# hv_io_precharge.net
KiCad netlist of a schematic drawn in Altium Designer
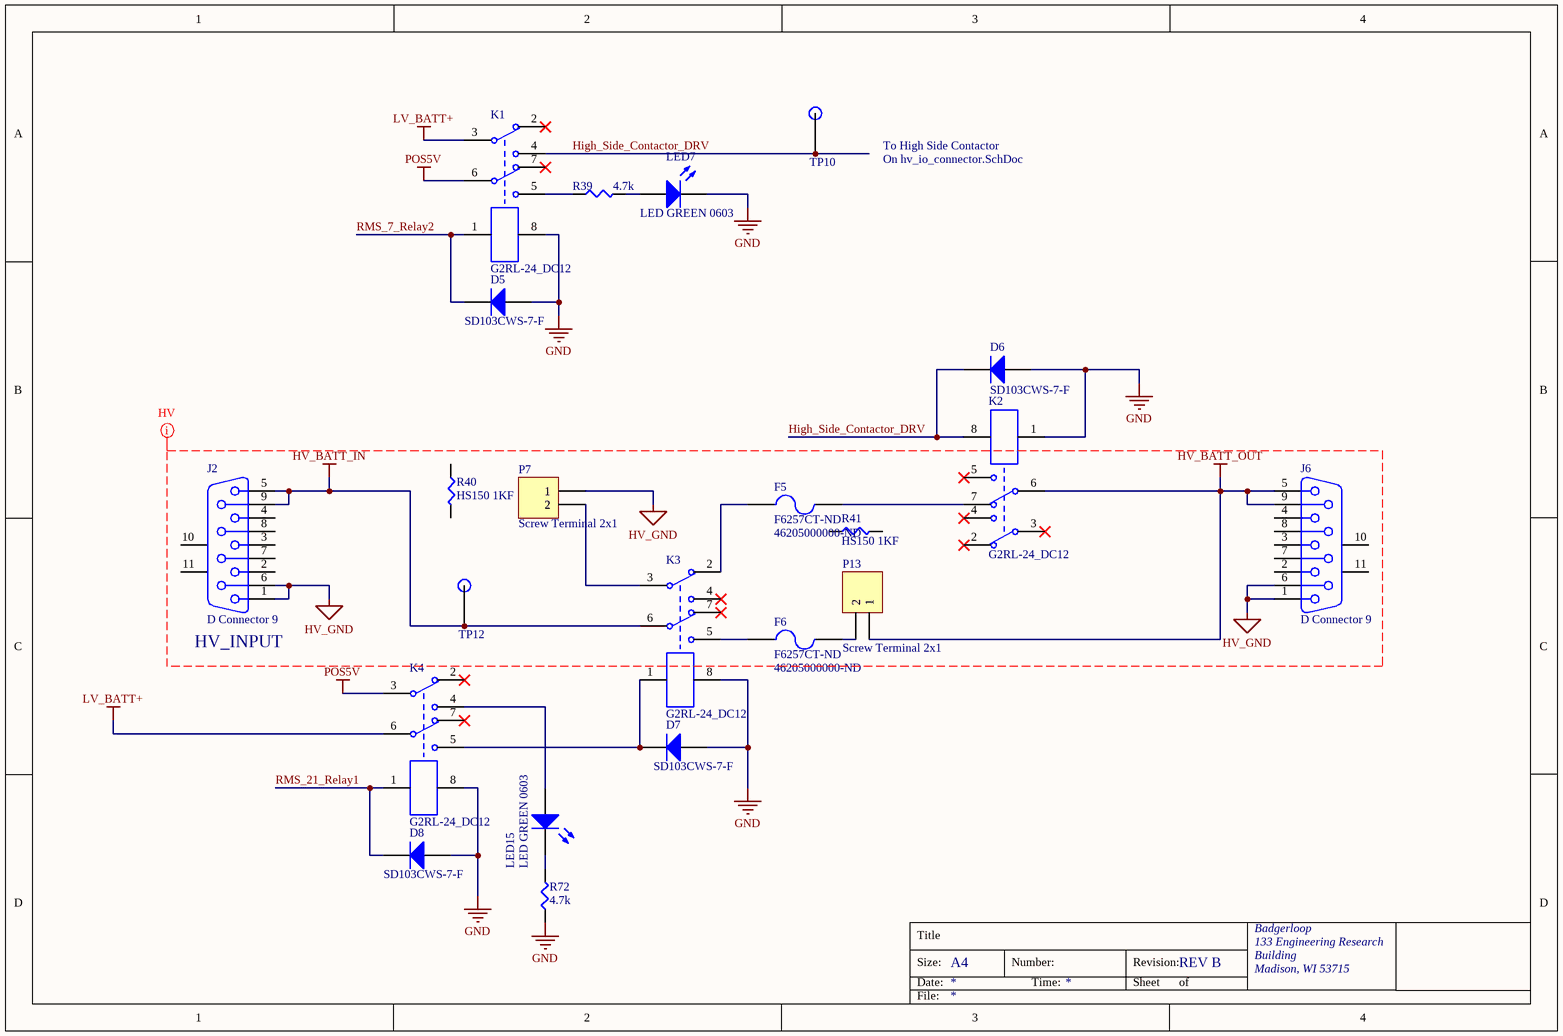
[diagram p0: hv_io_precharge.SchDoc]

(export (version "E")
  (design (tool "Eeschema 10.0.6"))
  (components
    (comp (ref "D5")
      (value "SD103CWS-7-F")
      (footprint "SODFL250X110-2N")
      (description "DIODE GEN PURP 20V 350MA SOD323")
      (fields (field (name "MANUFACTURER") "Diodes Incorporated"))
      (libsource (lib "misc") (part "Diode General Purpose_2"))
    )
    (comp (ref "D6")
      (value "SD103CWS-7-F")
      (footprint "SODFL250X110-2N")
      (description "DIODE GEN PURP 20V 350MA SOD323")
      (fields (field (name "MANUFACTURER") "Diodes Incorporated"))
      (libsource (lib "misc") (part "Diode General Purpose_2"))
    )
    (comp (ref "D7")
      (value "SD103CWS-7-F")
      (footprint "SODFL250X110-2N")
      (description "DIODE GEN PURP 20V 350MA SOD323")
      (fields (field (name "MANUFACTURER") "Diodes Incorporated"))
      (libsource (lib "misc") (part "Diode General Purpose_2"))
    )
    (comp (ref "D8")
      (value "SD103CWS-7-F")
      (footprint "SODFL250X110-2N")
      (description "DIODE GEN PURP 20V 350MA SOD323")
      (fields (field (name "MANUFACTURER") "Diodes Incorporated"))
      (libsource (lib "misc") (part "Diode General Purpose_2"))
    )
    (comp (ref "F5")
      (value "F6257CT-ND")
      (footprint "F6257CT-ND")
      (description "FUSE BOARD MNT 500MA 350VAC/VDC")
      (fields
        (field (name "MANUFACTURER") "Littelfuse")
        (field (name "MANUFACTURER PART NUMBER") "46205000000")
        (field (name "SUPPLIER PART NUMBER 1") "46205000000-ND")
      )
      (libsource (lib "misc") (part "F6257CT-ND"))
    )
    (comp (ref "F6")
      (value "F6257CT-ND")
      (footprint "F6257CT-ND")
      (description "FUSE BOARD MNT 500MA 350VAC/VDC")
      (fields
        (field (name "MANUFACTURER") "Littelfuse")
        (field (name "MANUFACTURER PART NUMBER") "46205000000")
        (field (name "SUPPLIER PART NUMBER 1") "46205000000-ND")
      )
      (libsource (lib "misc") (part "F6257CT-ND"))
    )
    (comp (ref "J2")
      (value "D Connector 9")
      (footprint "DSUB1.385-2H9")
      (description "Receptacle Assembly, 9 Position, Right Angle")
      (fields (field (name "PUBLISHER") "Altium Limited"))
      (libsource (lib "altium-import") (part "root_1_D Connector 9_"))
    )
    (comp (ref "J6")
      (value "D Connector 9")
      (footprint "DSUB1.385-2H9")
      (description "Receptacle Assembly, 9 Position, Right Angle")
      (fields (field (name "PUBLISHER") "Altium Limited"))
      (libsource (lib "altium-import") (part "root_1_mirrored_D Connector 9_"))
    )
    (comp (ref "K1")
      (value "G2RL-24_DC12")
      (footprint "G2RL")
      (description "RELAY GEN PURPOSE DPDT 8A 12V")
      (fields (field (name "MANUFACTURER") "Omron Electronics"))
      (libsource (lib "misc") (part "G2RL-24_DC12"))
    )
    (comp (ref "K2")
      (value "G2RL-24_DC12")
      (footprint "G2RL")
      (description "RELAY GEN PURPOSE DPDT 8A 12V")
      (fields (field (name "MANUFACTURER") "Omron Electronics"))
      (libsource (lib "misc") (part "G2RL-24_DC12"))
    )
    (comp (ref "K3")
      (value "G2RL-24_DC12")
      (footprint "G2RL")
      (description "RELAY GEN PURPOSE DPDT 8A 12V")
      (fields (field (name "MANUFACTURER") "Omron Electronics"))
      (libsource (lib "misc") (part "G2RL-24_DC12"))
    )
    (comp (ref "K4")
      (value "G2RL-24_DC12")
      (footprint "G2RL")
      (description "RELAY GEN PURPOSE DPDT 8A 12V")
      (fields (field (name "MANUFACTURER") "Omron Electronics"))
      (libsource (lib "misc") (part "G2RL-24_DC12"))
    )
    (comp (ref "LED7")
      (value "LED GREEN 0603")
      (footprint "LED 0603 GREEN")
      (fields (field (name "MANUFACTURER") "Lite-On Inc."))
      (libsource (lib "misc") (part "LED GREEN 0603"))
    )
    (comp (ref "LED15")
      (value "LED GREEN 0603")
      (footprint "LED 0603 GREEN")
      (fields (field (name "MANUFACTURER") "Lite-On Inc."))
      (libsource (lib "misc") (part "LED GREEN 0603"))
    )
    (comp (ref "P7")
      (value "Screw Terminal 2x1")
      (footprint "2POS TERM BLOCK")
      (description "Screw Terminal, 2-Pin")
      (libsource (lib "") (part "Screw Terminal 2x1_1"))
    )
    (comp (ref "P13")
      (value "Screw Terminal 2x1")
      (footprint "2POS TERM BLOCK")
      (description "Screw Terminal, 2-Pin")
      (libsource (lib "connector") (part "Screw Terminal 2x1"))
    )
    (comp (ref "R39")
      (value "4.7k")
      (footprint "SMD-0402-RES")
      (description "RES SMD 4.7K OHM 5% 1/10W 0402")
      (fields (field (name "PART NUMBER") "ERJ-2GEJ472X") (field (name "DIGI-KEY PART NUMBER") "P4.7KJCT-ND"))
      (libsource (lib "resistor") (part "ERJ-2GEJ472X"))
    )
    (comp (ref "R40")
      (value "HS150 1KF")
      (footprint "HS150 1KF")
      (description "1K Power Resistor")
      (fields (field (name "MANUFACTURER") "Ohmite"))
      (libsource (lib "temp") (part "HS150 1KF"))
    )
    (comp (ref "R41")
      (value "HS150 1KF")
      (footprint "HS150 1KF")
      (description "1K Power Resistor")
      (fields (field (name "MANUFACTURER") "Ohmite"))
      (libsource (lib "temp") (part "HS150 1KF"))
    )
    (comp (ref "R72")
      (value "4.7k")
      (footprint "SMD-0402-RES")
      (description "RES SMD 4.7K OHM 5% 1/10W 0402")
      (fields (field (name "PART NUMBER") "ERJ-2GEJ472X") (field (name "DIGI-KEY PART NUMBER") "P4.7KJCT-ND"))
      (libsource (lib "resistor") (part "ERJ-2GEJ472X"))
    )
    (comp (ref "TP10") (value "TP") (footprint "Test Point") (libsource (lib "misc") (part "TP")))
    (comp (ref "TP12") (value "TP") (footprint "Test Point") (libsource (lib "misc") (part "TP")))
  )
  (nets
    (net (code "1") (name "/High_Side_Contactor_DRV") (class "Default")
      (node (ref "D6") (pin "2") (pinfunction "K_2") (pintype "passive"))
      (node (ref "K1") (pin "4") (pinfunction "4_4") (pintype "passive"))
      (node (ref "K2") (pin "8") (pinfunction "8_8") (pintype "passive"))
      (node (ref "TP10") (pin "1") (pinfunction "1_1") (pintype "passive"))
    )
    (net (code "2") (name "/RMS_7_Relay2") (class "Default")
      (node (ref "D5") (pin "2") (pinfunction "K_2") (pintype "passive"))
      (node (ref "K1") (pin "1") (pinfunction "1_1") (pintype "passive"))
    )
    (net (code "3") (name "/RMS_21_Relay1") (class "Default")
      (node (ref "D8") (pin "2") (pinfunction "K_2") (pintype "passive"))
      (node (ref "K4") (pin "1") (pinfunction "1_1") (pintype "passive"))
    )
    (net (code "4") (name "GND") (class "Default")
      (node (ref "D5") (pin "1") (pinfunction "A_1") (pintype "passive"))
      (node (ref "D6") (pin "1") (pinfunction "A_1") (pintype "passive"))
      (node (ref "D7") (pin "1") (pinfunction "A_1") (pintype "passive"))
      (node (ref "D8") (pin "1") (pinfunction "A_1") (pintype "passive"))
      (node (ref "K1") (pin "8") (pinfunction "8_8") (pintype "passive"))
      (node (ref "K2") (pin "1") (pinfunction "1_1") (pintype "passive"))
      (node (ref "K3") (pin "8") (pinfunction "8_8") (pintype "passive"))
      (node (ref "K4") (pin "8") (pinfunction "8_8") (pintype "passive"))
      (node (ref "LED7") (pin "2") (pinfunction "K_2") (pintype "passive"))
      (node (ref "R72") (pin "1") (pinfunction "1_1") (pintype "passive"))
    )
    (net (code "5") (name "HV_BATT_IN") (class "Default")
      (node (ref "J2") (pin "5") (pinfunction "5_5") (pintype "passive"))
      (node (ref "J2") (pin "9") (pinfunction "9_9") (pintype "passive"))
      (node (ref "K3") (pin "6") (pinfunction "6_6") (pintype "passive"))
      (node (ref "TP12") (pin "1") (pinfunction "1_1") (pintype "passive"))
    )
    (net (code "6") (name "HV_BATT_OUT") (class "Default")
      (node (ref "J6") (pin "5") (pinfunction "5_5") (pintype "passive"))
      (node (ref "J6") (pin "9") (pinfunction "9_9") (pintype "passive"))
      (node (ref "K2") (pin "6") (pinfunction "6_6") (pintype "passive"))
      (node (ref "P13") (pin "1") (pinfunction "1_1") (pintype "passive"))
    )
    (net (code "7") (name "HV_GND") (class "Default")
      (node (ref "J2") (pin "1") (pinfunction "1_1") (pintype "passive"))
      (node (ref "J2") (pin "6") (pinfunction "6_6") (pintype "passive"))
      (node (ref "J6") (pin "1") (pinfunction "1_1") (pintype "passive"))
      (node (ref "J6") (pin "6") (pinfunction "6_6") (pintype "passive"))
      (node (ref "P7") (pin "1") (pinfunction "1_1") (pintype "passive"))
    )
    (net (code "8") (name "LV_BATT+") (class "Default")
      (node (ref "K1") (pin "3") (pinfunction "3_3") (pintype "passive"))
      (node (ref "K4") (pin "6") (pinfunction "6_6") (pintype "passive"))
    )
    (net (code "9") (name "Net-(D7-K)") (class "Default")
      (node (ref "D7") (pin "2") (pinfunction "K_2") (pintype "passive"))
      (node (ref "K3") (pin "1") (pinfunction "1_1") (pintype "passive"))
      (node (ref "K4") (pin "5") (pinfunction "5_5") (pintype "passive"))
    )
    (net (code "10") (name "Net-(F5-Pad1)") (class "Default")
      (node (ref "F5") (pin "1") (pinfunction "1_1") (pintype "passive"))
      (node (ref "K3") (pin "2") (pinfunction "2_2") (pintype "passive"))
    )
    (net (code "11") (name "Net-(F5-Pad2)") (class "Default")
      (node (ref "F5") (pin "2") (pinfunction "2_2") (pintype "passive"))
      (node (ref "K2") (pin "7") (pinfunction "7_7") (pintype "passive"))
    )
    (net (code "12") (name "Net-(F6-Pad1)") (class "Default")
      (node (ref "F6") (pin "1") (pinfunction "1_1") (pintype "passive"))
      (node (ref "K3") (pin "5") (pinfunction "5_5") (pintype "passive"))
    )
    (net (code "13") (name "Net-(F6-Pad2)") (class "Default")
      (node (ref "F6") (pin "2") (pinfunction "2_2") (pintype "passive"))
      (node (ref "P13") (pin "2") (pinfunction "2_2") (pintype "passive"))
    )
    (net (code "14") (name "Net-(K1-Pad5)") (class "Default")
      (node (ref "K1") (pin "5") (pinfunction "5_5") (pintype "passive"))
      (node (ref "R39") (pin "1") (pinfunction "1_1") (pintype "passive"))
    )
    (net (code "15") (name "Net-(K3-Pad3)") (class "Default")
      (node (ref "K3") (pin "3") (pinfunction "3_3") (pintype "passive"))
      (node (ref "P7") (pin "2") (pinfunction "2_2") (pintype "passive"))
    )
    (net (code "16") (name "Net-(LED7-A)") (class "Default")
      (node (ref "LED7") (pin "1") (pinfunction "A_1") (pintype "passive"))
      (node (ref "R39") (pin "2") (pinfunction "2_2") (pintype "passive"))
    )
    (net (code "17") (name "Net-(LED15-A)") (class "Default")
      (node (ref "K4") (pin "4") (pinfunction "4_4") (pintype "passive"))
      (node (ref "LED15") (pin "1") (pinfunction "A_1") (pintype "passive"))
    )
    (net (code "18") (name "Net-(LED15-K)") (class "Default")
      (node (ref "LED15") (pin "2") (pinfunction "K_2") (pintype "passive"))
      (node (ref "R72") (pin "2") (pinfunction "2_2") (pintype "passive"))
    )
    (net (code "19") (name "POS5V") (class "Default")
      (node (ref "K1") (pin "6") (pinfunction "6_6") (pintype "passive"))
      (node (ref "K4") (pin "3") (pinfunction "3_3") (pintype "passive"))
    )
    (net (code "20") (name "unconnected-(J2-MH1-Pad10)") (class "Default")
      (node (ref "J2") (pin "10") (pinfunction "MH1_10") (pintype "passive"))
    )
    (net (code "21") (name "unconnected-(J2-MH2-Pad11)") (class "Default")
      (node (ref "J2") (pin "11") (pinfunction "MH2_11") (pintype "passive"))
    )
    (net (code "22") (name "unconnected-(J2-Pad2)") (class "Default")
      (node (ref "J2") (pin "2") (pinfunction "2_2") (pintype "passive"))
    )
    (net (code "23") (name "unconnected-(J2-Pad3)") (class "Default")
      (node (ref "J2") (pin "3") (pinfunction "3_3") (pintype "passive"))
    )
    (net (code "24") (name "unconnected-(J2-Pad4)") (class "Default")
      (node (ref "J2") (pin "4") (pinfunction "4_4") (pintype "passive"))
    )
    (net (code "25") (name "unconnected-(J2-Pad7)") (class "Default")
      (node (ref "J2") (pin "7") (pinfunction "7_7") (pintype "passive"))
    )
    (net (code "26") (name "unconnected-(J2-Pad8)") (class "Default")
      (node (ref "J2") (pin "8") (pinfunction "8_8") (pintype "passive"))
    )
    (net (code "27") (name "unconnected-(J6-MH1-Pad10)") (class "Default")
      (node (ref "J6") (pin "10") (pinfunction "MH1_10") (pintype "passive"))
    )
    (net (code "28") (name "unconnected-(J6-MH2-Pad11)") (class "Default")
      (node (ref "J6") (pin "11") (pinfunction "MH2_11") (pintype "passive"))
    )
    (net (code "29") (name "unconnected-(J6-Pad2)") (class "Default")
      (node (ref "J6") (pin "2") (pinfunction "2_2") (pintype "passive"))
    )
    (net (code "30") (name "unconnected-(J6-Pad3)") (class "Default")
      (node (ref "J6") (pin "3") (pinfunction "3_3") (pintype "passive"))
    )
    (net (code "31") (name "unconnected-(J6-Pad4)") (class "Default")
      (node (ref "J6") (pin "4") (pinfunction "4_4") (pintype "passive"))
    )
    (net (code "32") (name "unconnected-(J6-Pad7)") (class "Default")
      (node (ref "J6") (pin "7") (pinfunction "7_7") (pintype "passive"))
    )
    (net (code "33") (name "unconnected-(J6-Pad8)") (class "Default")
      (node (ref "J6") (pin "8") (pinfunction "8_8") (pintype "passive"))
    )
    (net (code "34") (name "unconnected-(K1-Pad2)") (class "Default")
      (node (ref "K1") (pin "2") (pinfunction "2_2") (pintype "passive+no_connect"))
    )
    (net (code "35") (name "unconnected-(K1-Pad7)") (class "Default")
      (node (ref "K1") (pin "7") (pinfunction "7_7") (pintype "passive+no_connect"))
    )
    (net (code "36") (name "unconnected-(K2-Pad2)") (class "Default")
      (node (ref "K2") (pin "2") (pinfunction "2_2") (pintype "passive+no_connect"))
    )
    (net (code "37") (name "unconnected-(K2-Pad3)") (class "Default")
      (node (ref "K2") (pin "3") (pinfunction "3_3") (pintype "passive+no_connect"))
    )
    (net (code "38") (name "unconnected-(K2-Pad4)") (class "Default")
      (node (ref "K2") (pin "4") (pinfunction "4_4") (pintype "passive+no_connect"))
    )
    (net (code "39") (name "unconnected-(K2-Pad5)") (class "Default")
      (node (ref "K2") (pin "5") (pinfunction "5_5") (pintype "passive+no_connect"))
    )
    (net (code "40") (name "unconnected-(K3-Pad4)") (class "Default")
      (node (ref "K3") (pin "4") (pinfunction "4_4") (pintype "passive+no_connect"))
    )
    (net (code "41") (name "unconnected-(K3-Pad7)") (class "Default")
      (node (ref "K3") (pin "7") (pinfunction "7_7") (pintype "passive+no_connect"))
    )
    (net (code "42") (name "unconnected-(K4-Pad2)") (class "Default")
      (node (ref "K4") (pin "2") (pinfunction "2_2") (pintype "passive+no_connect"))
    )
    (net (code "43") (name "unconnected-(K4-Pad7)") (class "Default")
      (node (ref "K4") (pin "7") (pinfunction "7_7") (pintype "passive+no_connect"))
    )
    (net (code "44") (name "unconnected-(R40-Pad1)") (class "Default")
      (node (ref "R40") (pin "1") (pinfunction "1_1") (pintype "passive"))
    )
    (net (code "45") (name "unconnected-(R40-Pad2)") (class "Default")
      (node (ref "R40") (pin "2") (pinfunction "2_2") (pintype "passive"))
    )
    (net (code "46") (name "unconnected-(R41-Pad1)") (class "Default")
      (node (ref "R41") (pin "1") (pinfunction "1_1") (pintype "passive"))
    )
    (net (code "47") (name "unconnected-(R41-Pad2)") (class "Default")
      (node (ref "R41") (pin "2") (pinfunction "2_2") (pintype "passive"))
    )
  )
)
